# LINEAR_VOLTAGE_REG.net
KiCad netlist of a schematic drawn in Altium Designer
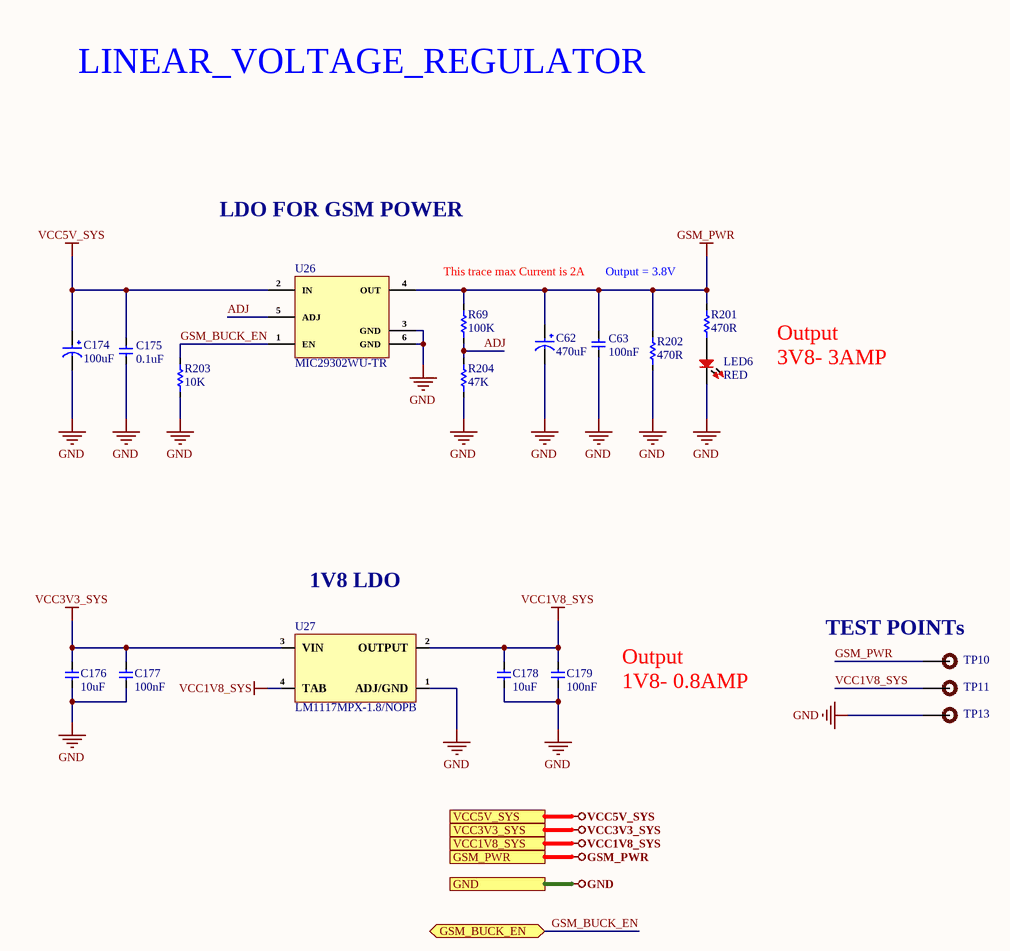
[diagram p0: LINEAR_VOLTAGE_REG.SchDoc]

(export (version "E")
  (design (tool "Eeschema 10.0.6"))
  (components
    (comp (ref "C62")
      (value "470uF")
      (footprint "Case-E")
      (description "CAP TANT 470UF 10% 10V 2917")
      (fields
        (field (name "MANUFACTURER") "Kyocera AVX")
        (field (name "MANUFACTURER PART NUMBER") "TAJE477K010RNJ")
      )
      (libsource (lib "eSpark Libraries") (part "TAJE477K010RNJ"))
    )
    (comp (ref "C63")
      (value "100nF")
      (footprint "Cap-0603")
      (description "CAP CER 0.1UF 50V X5R 0603")
      (fields
        (field (name "MANUFACTURER") "Yageo")
        (field (name "MANUFACTURER PART NUMBER") "CC0603KRX5R9BB104")
      )
      (libsource (lib "eSpark Libraries") (part "CC0603KRX5R9BB104"))
    )
    (comp (ref "C174")
      (value "100uF")
      (footprint "Case-B")
      (description "CAP TANT 100UF 20% 10V 1411")
      (fields
        (field (name "MANUFACTURER") "Kyocera AVX")
        (field (name "MANUFACTURER PART NUMBER") "TAJB107M010RNJ")
      )
      (libsource (lib "eSpark Libraries") (part "TAJB107M010RNJ"))
    )
    (comp (ref "C175")
      (value "0.1uF")
      (footprint "Cap-0603")
      (description "CAP CER 0.1UF 100V X7R 0603")
      (fields
        (field (name "MANUFACTURER") "Yageo")
        (field (name "MANUFACTURER PART NUMBER") "CC0603KRX7R0BB104")
      )
      (libsource (lib "eSpark Libraries") (part "CC0603KRX7R0BB104"))
    )
    (comp (ref "C176")
      (value "10uF")
      (footprint "Cap-0805")
      (description "CAP CER 10UF 50V X5R 0805")
      (fields
        (field (name "MANUFACTURER") "Murata")
        (field (name "MANUFACTURER PART NUMBER") "GRM21BR61H106ME43L")
      )
      (libsource (lib "eSpark Libraries") (part "GRM21BR61H106ME43L"))
    )
    (comp (ref "C177")
      (value "100nF")
      (footprint "cap-0402")
      (description "CAP CER 0.1UF 50V X7R 0402")
      (fields
        (field (name "MANUFACTURER") "TDK")
        (field (name "MANUFACTURER PART NUMBER") "C1005X7R1H104KT000F")
      )
      (libsource (lib "eSpark Libraries") (part "C1005X7R1H104KT000F"))
    )
    (comp (ref "C178")
      (value "10uF")
      (footprint "Cap-0805")
      (description "CAP CER 10UF 50V X5R 0805")
      (fields
        (field (name "MANUFACTURER") "Murata")
        (field (name "MANUFACTURER PART NUMBER") "GRM21BR61H106ME43L")
      )
      (libsource (lib "eSpark Libraries") (part "GRM21BR61H106ME43L"))
    )
    (comp (ref "C179")
      (value "100nF")
      (footprint "cap-0402")
      (description "CAP CER 0.1UF 50V X7R 0402")
      (fields
        (field (name "MANUFACTURER") "TDK")
        (field (name "MANUFACTURER PART NUMBER") "C1005X7R1H104KT000F")
      )
      (libsource (lib "eSpark Libraries") (part "C1005X7R1H104KT000F"))
    )
    (comp (ref "LED6")
      (value "RED")
      (footprint "LED-0603")
      (description "RED LED 0603 Light Emitting Diodes")
      (fields
        (field (name "MANUFACTURER") "Foshan NationStar Optoelectronics")
        (field (name "MANUFACTURER PART NUMBER") "NCD0603R3")
      )
      (libsource (lib "eSpark Libraries") (part "NCD0603R3"))
    )
    (comp (ref "R69")
      (value "100K")
      (footprint "Res-0402")
      (description "RES 100K OHM 1% 1/16W 0402")
      (fields
        (field (name "MANUFACTURER") "Yageo")
        (field (name "MANUFACTURER PART NUMBER") "RC0402FR-07100KL")
      )
      (libsource (lib "eSpark Libraries") (part "RC0402FR-07100KL"))
    )
    (comp (ref "R201")
      (value "470R")
      (footprint "Res-0603")
      (description "RES 470 OHM 1% 1/10W 0603")
      (fields
        (field (name "MANUFACTURER") "Yageo")
        (field (name "MANUFACTURER PART NUMBER") "RC0603FR-07470RL")
      )
      (libsource (lib "eSpark Libraries") (part "RC0603FR-07470RL"))
    )
    (comp (ref "R202")
      (value "470R")
      (footprint "Res-0603")
      (description "RES 470 OHM 1% 1/10W 0603")
      (fields
        (field (name "MANUFACTURER") "Yageo")
        (field (name "MANUFACTURER PART NUMBER") "RC0603FR-07470RL")
      )
      (libsource (lib "eSpark Libraries") (part "RC0603FR-07470RL"))
    )
    (comp (ref "R203")
      (value "10K")
      (footprint "Res-0402")
      (description "RES 10K OHM 1% 1/16W 0402")
      (fields
        (field (name "MANUFACTURER") "Yageo")
        (field (name "MANUFACTURER PART NUMBER") "RC0402FR-0710KL")
      )
      (libsource (lib "eSpark Libraries") (part "RC0402FR-0710KL"))
    )
    (comp (ref "R204")
      (value "47K")
      (footprint "Res-0402")
      (description "RES 47K OHM 1% 1/16W 0402")
      (fields
        (field (name "MANUFACTURER") "Yageo")
        (field (name "MANUFACTURER PART NUMBER") "RC0402FR-0747KL")
      )
      (libsource (lib "eSpark Libraries") (part "RC0402FR-0747KL"))
    )
    (comp (ref "TP10")
      (value "TEST POINT 0.5mm Dia")
      (footprint "Test-point - 0.5mm")
      (description "Test Point ON")
      (libsource (lib "eSpark Libraries") (part "TEST POINT 0.5mm Dia"))
    )
    (comp (ref "TP11")
      (value "TEST POINT 0.5mm Dia")
      (footprint "Test-point - 0.5mm")
      (description "Test Point ON")
      (libsource (lib "eSpark Libraries") (part "TEST POINT 0.5mm Dia"))
    )
    (comp (ref "TP13")
      (value "TEST POINT 0.5mm Dia")
      (footprint "Test-point - 0.5mm")
      (description "Test Point ON")
      (libsource (lib "eSpark Libraries") (part "TEST POINT 0.5mm Dia"))
    )
    (comp (ref "U26")
      (value "MIC29302WU-TR")
      (footprint "TO-263-5 (D2PAK)")
      (description "IC REG LDO ADJ 3A TO263-5")
      (fields (field (name "MANUFACTURER") "Microchip") (field (name "LCSC PART NUMBER") "C11149"))
      (libsource (lib "eSpark Libraries") (part "MIC29302WU-TR"))
    )
    (comp (ref "U27")
      (value "LM1117MPX-1.8/NOPB")
      (footprint "SOT- 223")
      (description "IC REG LINEAR 1.8V 800MA SOT223")
      (fields
        (field (name "MANUFACTURER") "TI National Semiconductor")
        (field (name "LCSC PART NUMBER") "C9660")
      )
      (libsource (lib "eSpark Libraries") (part "LM1117MPX-1.8/NOPB"))
    )
  )
  (nets
    (net (code "1") (name "/ADJ") (class "Default")
      (node (ref "R204") (pin "2") (pinfunction "2_2") (pintype "passive"))
      (node (ref "R69") (pin "1") (pinfunction "1_1") (pintype "passive"))
      (node (ref "U26") (pin "5") (pinfunction "ADJ_5") (pintype "passive"))
    )
    (net (code "2") (name "/GSM_BUCK_EN") (class "Default")
      (node (ref "R203") (pin "2") (pinfunction "2_2") (pintype "passive"))
      (node (ref "U26") (pin "1") (pinfunction "EN_1") (pintype "passive"))
    )
    (net (code "3") (name "GND") (class "Default")
      (node (ref "C174") (pin "2") (pinfunction "2_2") (pintype "passive"))
      (node (ref "C175") (pin "1") (pinfunction "1_1") (pintype "passive"))
      (node (ref "C176") (pin "1") (pinfunction "1_1") (pintype "passive"))
      (node (ref "C177") (pin "1") (pinfunction "1_1") (pintype "passive"))
      (node (ref "C178") (pin "1") (pinfunction "1_1") (pintype "passive"))
      (node (ref "C179") (pin "1") (pinfunction "1_1") (pintype "passive"))
      (node (ref "C62") (pin "2") (pinfunction "2_2") (pintype "passive"))
      (node (ref "C63") (pin "1") (pinfunction "1_1") (pintype "passive"))
      (node (ref "LED6") (pin "2") (pinfunction "2_2") (pintype "passive"))
      (node (ref "R202") (pin "1") (pinfunction "1_1") (pintype "passive"))
      (node (ref "R203") (pin "1") (pinfunction "1_1") (pintype "passive"))
      (node (ref "R204") (pin "1") (pinfunction "1_1") (pintype "passive"))
      (node (ref "TP13") (pin "1") (pinfunction "1_1") (pintype "passive"))
      (node (ref "U26") (pin "3") (pinfunction "GND_3") (pintype "passive"))
      (node (ref "U26") (pin "6") (pinfunction "GND_6") (pintype "passive"))
      (node (ref "U27") (pin "1") (pinfunction "ADJ/GND_1") (pintype "passive"))
    )
    (net (code "4") (name "GSM_PWR") (class "Default")
      (node (ref "C62") (pin "1") (pinfunction "1_1") (pintype "passive"))
      (node (ref "C63") (pin "2") (pinfunction "2_2") (pintype "passive"))
      (node (ref "R201") (pin "2") (pinfunction "2_2") (pintype "passive"))
      (node (ref "R202") (pin "2") (pinfunction "2_2") (pintype "passive"))
      (node (ref "R69") (pin "2") (pinfunction "2_2") (pintype "passive"))
      (node (ref "TP10") (pin "1") (pinfunction "1_1") (pintype "passive"))
      (node (ref "U26") (pin "4") (pinfunction "OUT_4") (pintype "passive"))
    )
    (net (code "5") (name "Net-(LED6-Pad1)") (class "Default")
      (node (ref "LED6") (pin "1") (pinfunction "1_1") (pintype "passive"))
      (node (ref "R201") (pin "1") (pinfunction "1_1") (pintype "passive"))
    )
    (net (code "6") (name "VCC1V8_SYS") (class "Default")
      (node (ref "C178") (pin "2") (pinfunction "2_2") (pintype "passive"))
      (node (ref "C179") (pin "2") (pinfunction "2_2") (pintype "passive"))
      (node (ref "TP11") (pin "1") (pinfunction "1_1") (pintype "passive"))
      (node (ref "U27") (pin "2") (pinfunction "OUTPUT_2") (pintype "passive"))
      (node (ref "U27") (pin "4") (pinfunction "TAB_4") (pintype "passive"))
    )
    (net (code "7") (name "VCC3V3_SYS") (class "Default")
      (node (ref "C176") (pin "2") (pinfunction "2_2") (pintype "passive"))
      (node (ref "C177") (pin "2") (pinfunction "2_2") (pintype "passive"))
      (node (ref "U27") (pin "3") (pinfunction "VIN_3") (pintype "passive"))
    )
    (net (code "8") (name "VCC5V_SYS") (class "Default")
      (node (ref "C174") (pin "1") (pinfunction "1_1") (pintype "passive"))
      (node (ref "C175") (pin "2") (pinfunction "2_2") (pintype "passive"))
      (node (ref "U26") (pin "2") (pinfunction "IN_2") (pintype "passive"))
    )
  )
)
